# Glove_PCB.net
KiCad netlist of a schematic drawn in EAGLE
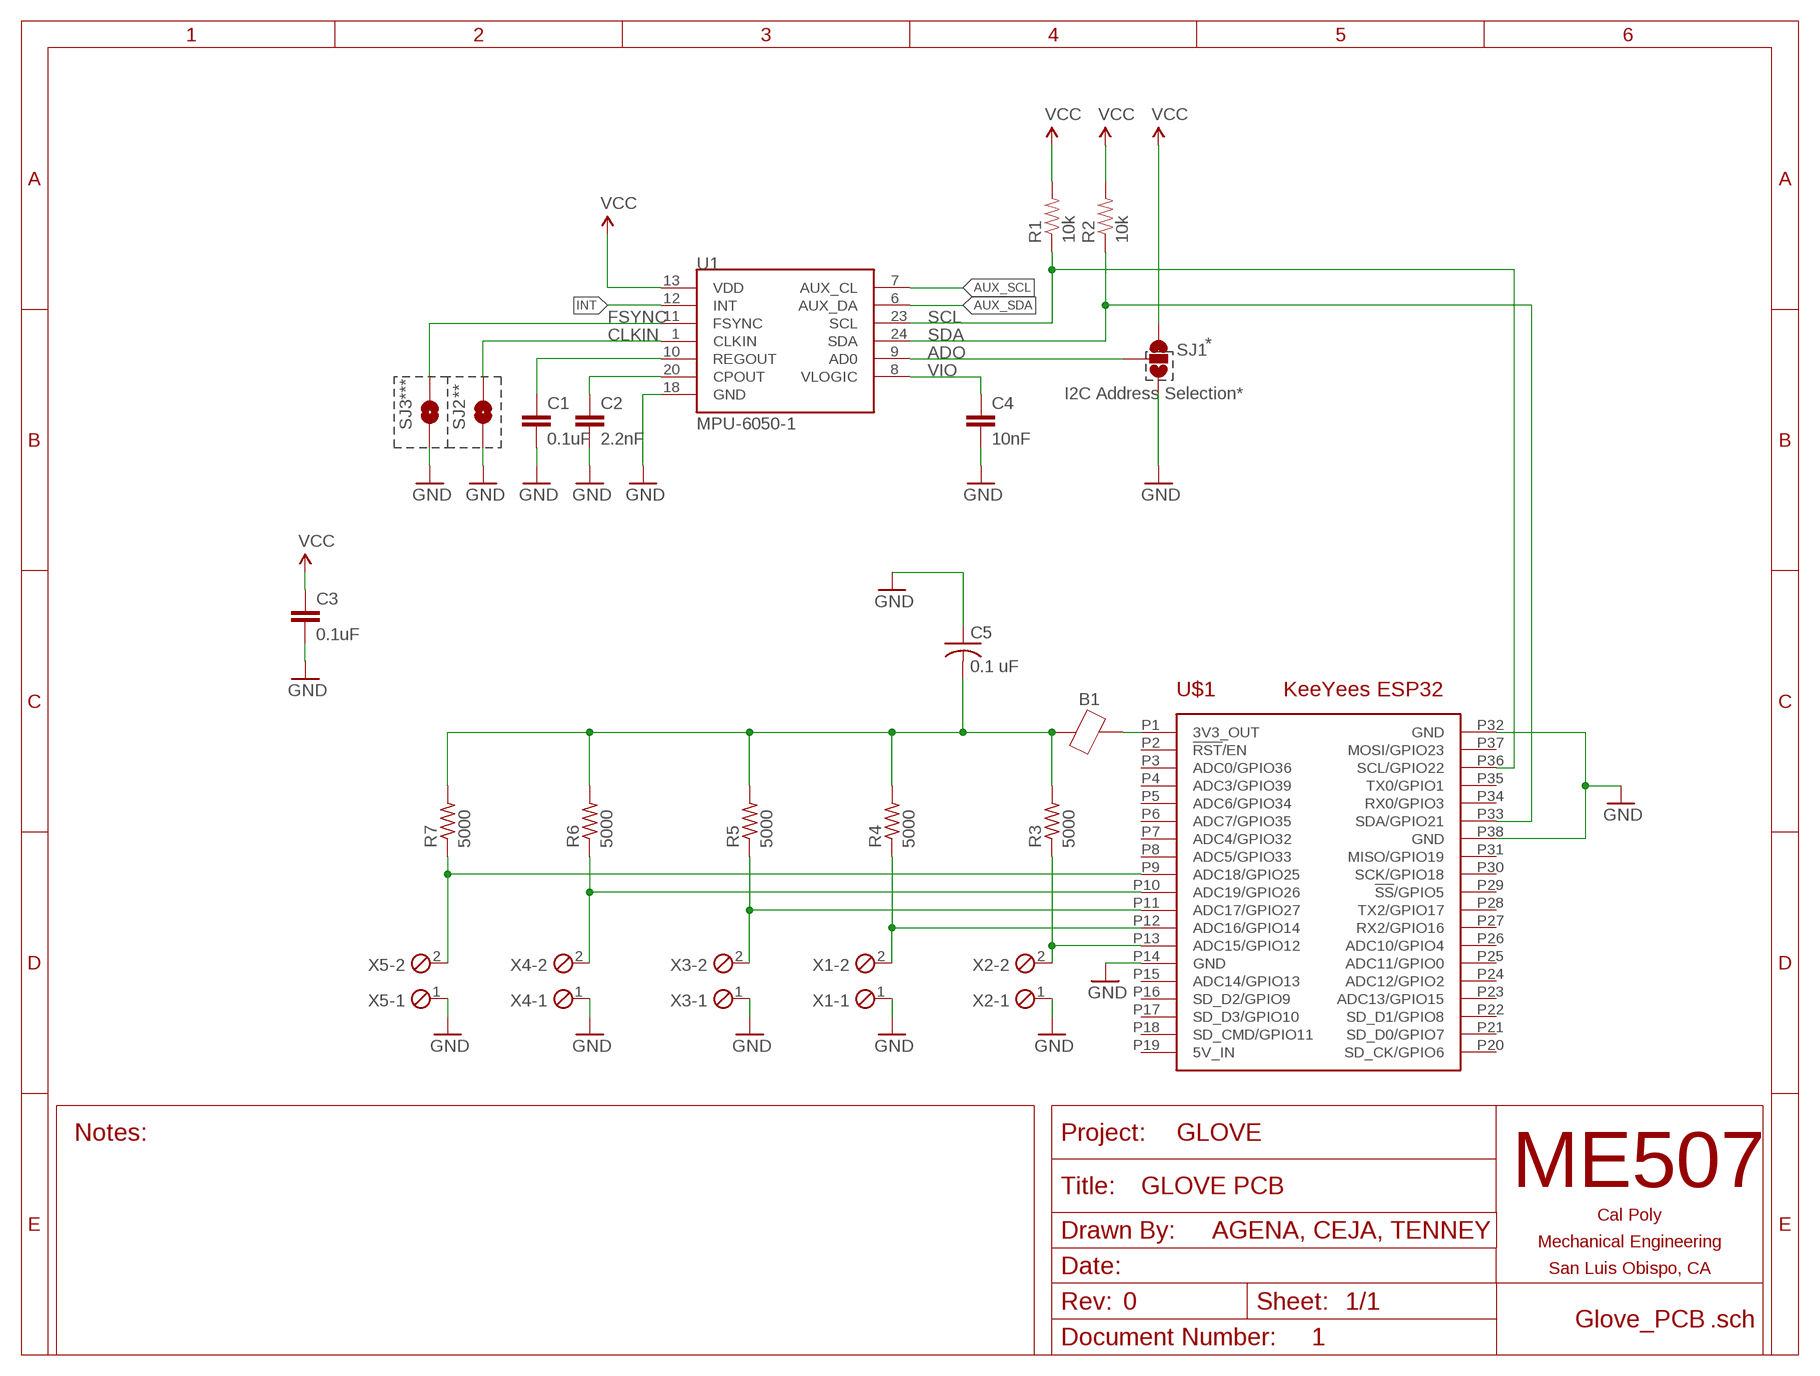
[diagram p0: schematic, sheet 1]

(export (version "E")
  (design (tool "Eeschema 10.0.6"))
  (components
    (comp (ref "B1")
      (value "BEAD0805")
      (footprint "eagle-import:0805")
      (libsource (lib "eagle-import") (part "BEAD0805"))
    )
    (comp (ref "C1")
      (value "0.1uF")
      (footprint "eagle-import:0603-CAP")
      (libsource (lib "eagle-import") (part "CAP0603-CAP"))
    )
    (comp (ref "C2")
      (value "2.2nF")
      (footprint "eagle-import:0603-CAP")
      (libsource (lib "eagle-import") (part "CAP0603-CAP"))
    )
    (comp (ref "C3")
      (value "0.1uF")
      (footprint "eagle-import:0603-CAP")
      (libsource (lib "eagle-import") (part "CAP0603-CAP"))
    )
    (comp (ref "C4")
      (value "10nF")
      (footprint "eagle-import:0603-CAP")
      (libsource (lib "eagle-import") (part "CAP0603-CAP"))
    )
    (comp (ref "C5")
      (value "0.1 uF")
      (footprint "eagle-import:C0805")
      (libsource (lib "eagle-import") (part "C-USC0805"))
    )
    (comp (ref "R1")
      (value "10k")
      (footprint "eagle-import:0603-RES")
      (libsource (lib "eagle-import") (part "RESISTOR0603-RES"))
    )
    (comp (ref "R2")
      (value "10k")
      (footprint "eagle-import:0603-RES")
      (libsource (lib "eagle-import") (part "RESISTOR0603-RES"))
    )
    (comp (ref "R3")
      (value "5000")
      (footprint "eagle-import:R0805")
      (libsource (lib "eagle-import") (part "R-US_R0805"))
    )
    (comp (ref "R4")
      (value "5000")
      (footprint "eagle-import:R0805")
      (libsource (lib "eagle-import") (part "R-US_R0805"))
    )
    (comp (ref "R5")
      (value "5000")
      (footprint "eagle-import:R0805")
      (libsource (lib "eagle-import") (part "R-US_R0805"))
    )
    (comp (ref "R6")
      (value "5000")
      (footprint "eagle-import:R0805")
      (libsource (lib "eagle-import") (part "R-US_R0805"))
    )
    (comp (ref "R7")
      (value "5000")
      (footprint "eagle-import:R0805")
      (libsource (lib "eagle-import") (part "R-US_R0805"))
    )
    (comp (ref "SJ1")
      (value "SOLDERJUMPER_2WAYPASTE2&3")
      (footprint "eagle-import:SJ_3_PASTE2&3")
      (libsource (lib "eagle-import") (part "SOLDERJUMPER_2WAYPASTE2&3"))
    )
    (comp (ref "SJ2")
      (value "SOLDERJUMPERTRACE")
      (footprint "eagle-import:SJ_2S-TRACE")
      (libsource (lib "eagle-import") (part "SOLDERJUMPERTRACE"))
    )
    (comp (ref "SJ3")
      (value "SOLDERJUMPERTRACE")
      (footprint "eagle-import:SJ_2S-TRACE")
      (libsource (lib "eagle-import") (part "SOLDERJUMPERTRACE"))
    )
    (comp (ref "U$1")
      (value "KEEYEES_ESP32EXT")
      (footprint "eagle-import:KEEYEES_ESP32_EXTENDED")
      (libsource (lib "eagle-import") (part "KEEYEES_ESP32EXT"))
    )
    (comp (ref "U1")
      (value "MPU-6050-1")
      (footprint "eagle-import:QFN-24-4MM2")
      (libsource (lib "eagle-import") (part "MPU-6050-1"))
    )
    (comp (ref "X1")
      (value "SCREWTERM_2P_254")
      (footprint "eagle-import:2POL254")
      (libsource (lib "eagle-import") (part "SCREWTERM_2P_254"))
    )
    (comp (ref "X2")
      (value "SCREWTERM_2P_254")
      (footprint "eagle-import:2POL254")
      (libsource (lib "eagle-import") (part "SCREWTERM_2P_254"))
    )
    (comp (ref "X3")
      (value "SCREWTERM_2P_254")
      (footprint "eagle-import:2POL254")
      (libsource (lib "eagle-import") (part "SCREWTERM_2P_254"))
    )
    (comp (ref "X4")
      (value "SCREWTERM_2P_254")
      (footprint "eagle-import:2POL254")
      (libsource (lib "eagle-import") (part "SCREWTERM_2P_254"))
    )
    (comp (ref "X5")
      (value "SCREWTERM_2P_254")
      (footprint "eagle-import:2POL254")
      (libsource (lib "eagle-import") (part "SCREWTERM_2P_254"))
    )
  )
  (nets
    (net (code "1") (name "/5V_IN") (class "Default")
      (node (ref "U$1") (pin "P19") (pinfunction "5V_IN_P19") (pintype "power_in"))
    )
    (net (code "2") (name "/ADO") (class "Default")
      (node (ref "SJ1") (pin "2") (pinfunction "2_2") (pintype "passive"))
      (node (ref "U1") (pin "9") (pinfunction "AD0_9") (pintype "bidirectional"))
    )
    (net (code "3") (name "/CLKIN") (class "Default")
      (node (ref "SJ2") (pin "2") (pinfunction "2_2") (pintype "passive"))
      (node (ref "U1") (pin "1") (pinfunction "CLKIN_1") (pintype "bidirectional"))
    )
    (net (code "4") (name "/FSYNC") (class "Default")
      (node (ref "SJ3") (pin "2") (pinfunction "2_2") (pintype "passive"))
      (node (ref "U1") (pin "11") (pinfunction "FSYNC_11") (pintype "bidirectional"))
    )
    (net (code "5") (name "/SCL") (class "Default")
      (node (ref "R1") (pin "1") (pinfunction "1_1") (pintype "passive"))
      (node (ref "U$1") (pin "P36") (pinfunction "SCL/GPIO22_P36") (pintype "bidirectional"))
      (node (ref "U1") (pin "23") (pinfunction "SCL_23") (pintype "bidirectional"))
    )
    (net (code "6") (name "/SDA") (class "Default")
      (node (ref "R2") (pin "1") (pinfunction "1_1") (pintype "passive"))
      (node (ref "U$1") (pin "P33") (pinfunction "SDA/GPIO21_P33") (pintype "bidirectional"))
      (node (ref "U1") (pin "24") (pinfunction "SDA_24") (pintype "bidirectional"))
    )
    (net (code "7") (name "/VIO") (class "Default")
      (node (ref "C4") (pin "1") (pinfunction "1_1") (pintype "passive"))
      (node (ref "U1") (pin "8") (pinfunction "VLOGIC_8") (pintype "bidirectional"))
    )
    (net (code "8") (name "AUX_SCL") (class "Default")
      (node (ref "U1") (pin "7") (pinfunction "AUX_CL_7") (pintype "bidirectional"))
    )
    (net (code "9") (name "AUX_SDA") (class "Default")
      (node (ref "U1") (pin "6") (pinfunction "AUX_DA_6") (pintype "bidirectional"))
    )
    (net (code "10") (name "GND") (class "Default")
      (node (ref "C1") (pin "2") (pinfunction "2_2") (pintype "passive"))
      (node (ref "C2") (pin "2") (pinfunction "2_2") (pintype "passive"))
      (node (ref "C3") (pin "2") (pinfunction "2_2") (pintype "passive"))
      (node (ref "C4") (pin "2") (pinfunction "2_2") (pintype "passive"))
      (node (ref "C5") (pin "1") (pinfunction "1_1") (pintype "passive"))
      (node (ref "SJ1") (pin "3") (pinfunction "3_3") (pintype "passive"))
      (node (ref "SJ2") (pin "1") (pinfunction "1_1") (pintype "passive"))
      (node (ref "SJ3") (pin "1") (pinfunction "1_1") (pintype "passive"))
      (node (ref "U$1") (pin "P14") (pinfunction "GND_P14") (pintype "power_in"))
      (node (ref "U$1") (pin "P32") (pinfunction "GND_P32") (pintype "power_in"))
      (node (ref "U$1") (pin "P38") (pinfunction "GND_P38") (pintype "power_in"))
      (node (ref "U1") (pin "18") (pinfunction "GND_18") (pintype "bidirectional"))
      (node (ref "X1") (pin "1") (pinfunction "1_1") (pintype "passive"))
      (node (ref "X2") (pin "1") (pinfunction "1_1") (pintype "passive"))
      (node (ref "X3") (pin "1") (pinfunction "1_1") (pintype "passive"))
      (node (ref "X4") (pin "1") (pinfunction "1_1") (pintype "passive"))
      (node (ref "X5") (pin "1") (pinfunction "1_1") (pintype "passive"))
    )
    (net (code "11") (name "INT") (class "Default")
      (node (ref "U1") (pin "12") (pinfunction "INT_12") (pintype "bidirectional"))
    )
    (net (code "12") (name "Net-(B1-Pad1)") (class "Default")
      (node (ref "B1") (pin "1") (pinfunction "1_1") (pintype "bidirectional"))
      (node (ref "C5") (pin "2") (pinfunction "2_2") (pintype "passive"))
      (node (ref "R3") (pin "2") (pinfunction "2_2") (pintype "passive"))
      (node (ref "R4") (pin "2") (pinfunction "2_2") (pintype "passive"))
      (node (ref "R5") (pin "2") (pinfunction "2_2") (pintype "passive"))
      (node (ref "R6") (pin "2") (pinfunction "2_2") (pintype "passive"))
      (node (ref "R7") (pin "2") (pinfunction "2_2") (pintype "passive"))
    )
    (net (code "13") (name "Net-(U$1-3V3_OUT)") (class "Default")
      (node (ref "B1") (pin "2") (pinfunction "2_2") (pintype "bidirectional"))
      (node (ref "U$1") (pin "P1") (pinfunction "3V3_OUT_P1") (pintype "power_in"))
    )
    (net (code "14") (name "Net-(U$1-ADC15{slash}GPIO12)") (class "Default")
      (node (ref "R3") (pin "1") (pinfunction "1_1") (pintype "passive"))
      (node (ref "U$1") (pin "P13") (pinfunction "ADC15/GPIO12_P13") (pintype "bidirectional"))
      (node (ref "X2") (pin "2") (pinfunction "1_2") (pintype "passive"))
    )
    (net (code "15") (name "Net-(U$1-ADC16{slash}GPIO14)") (class "Default")
      (node (ref "R4") (pin "1") (pinfunction "1_1") (pintype "passive"))
      (node (ref "U$1") (pin "P12") (pinfunction "ADC16/GPIO14_P12") (pintype "bidirectional"))
      (node (ref "X1") (pin "2") (pinfunction "1_2") (pintype "passive"))
    )
    (net (code "16") (name "Net-(U$1-ADC17{slash}GPIO27)") (class "Default")
      (node (ref "R5") (pin "1") (pinfunction "1_1") (pintype "passive"))
      (node (ref "U$1") (pin "P11") (pinfunction "ADC17/GPIO27_P11") (pintype "bidirectional"))
      (node (ref "X3") (pin "2") (pinfunction "1_2") (pintype "passive"))
    )
    (net (code "17") (name "Net-(U$1-ADC18{slash}GPIO25)") (class "Default")
      (node (ref "R7") (pin "1") (pinfunction "1_1") (pintype "passive"))
      (node (ref "U$1") (pin "P9") (pinfunction "ADC18/GPIO25_P9") (pintype "bidirectional"))
      (node (ref "X5") (pin "2") (pinfunction "1_2") (pintype "passive"))
    )
    (net (code "18") (name "Net-(U$1-ADC19{slash}GPIO26)") (class "Default")
      (node (ref "R6") (pin "1") (pinfunction "1_1") (pintype "passive"))
      (node (ref "U$1") (pin "P10") (pinfunction "ADC19/GPIO26_P10") (pintype "bidirectional"))
      (node (ref "X4") (pin "2") (pinfunction "1_2") (pintype "passive"))
    )
    (net (code "19") (name "Net-(U1-CPOUT)") (class "Default")
      (node (ref "C2") (pin "1") (pinfunction "1_1") (pintype "passive"))
      (node (ref "U1") (pin "20") (pinfunction "CPOUT_20") (pintype "bidirectional"))
    )
    (net (code "20") (name "Net-(U1-REGOUT)") (class "Default")
      (node (ref "C1") (pin "1") (pinfunction "1_1") (pintype "passive"))
      (node (ref "U1") (pin "10") (pinfunction "REGOUT_10") (pintype "bidirectional"))
    )
    (net (code "21") (name "VCC") (class "Default")
      (node (ref "C3") (pin "1") (pinfunction "1_1") (pintype "passive"))
      (node (ref "R1") (pin "2") (pinfunction "2_2") (pintype "passive"))
      (node (ref "R2") (pin "2") (pinfunction "2_2") (pintype "passive"))
      (node (ref "SJ1") (pin "1") (pinfunction "1_1") (pintype "passive"))
      (node (ref "U1") (pin "13") (pinfunction "VDD_13") (pintype "bidirectional"))
    )
    (net (code "22") (name "unconnected-(U$1-ADC0{slash}GPIO36-PadP3)") (class "Default")
      (node (ref "U$1") (pin "P3") (pinfunction "ADC0/GPIO36_P3") (pintype "bidirectional"))
    )
    (net (code "23") (name "unconnected-(U$1-ADC3{slash}GPIO39-PadP4)") (class "Default")
      (node (ref "U$1") (pin "P4") (pinfunction "ADC3/GPIO39_P4") (pintype "bidirectional"))
    )
    (net (code "24") (name "unconnected-(U$1-ADC4{slash}GPIO32-PadP7)") (class "Default")
      (node (ref "U$1") (pin "P7") (pinfunction "ADC4/GPIO32_P7") (pintype "bidirectional"))
    )
    (net (code "25") (name "unconnected-(U$1-ADC5{slash}GPIO33-PadP8)") (class "Default")
      (node (ref "U$1") (pin "P8") (pinfunction "ADC5/GPIO33_P8") (pintype "bidirectional"))
    )
    (net (code "26") (name "unconnected-(U$1-ADC6{slash}GPIO34-PadP5)") (class "Default")
      (node (ref "U$1") (pin "P5") (pinfunction "ADC6/GPIO34_P5") (pintype "bidirectional"))
    )
    (net (code "27") (name "unconnected-(U$1-ADC7{slash}GPIO35-PadP6)") (class "Default")
      (node (ref "U$1") (pin "P6") (pinfunction "ADC7/GPIO35_P6") (pintype "bidirectional"))
    )
    (net (code "28") (name "unconnected-(U$1-ADC10{slash}GPIO4-PadP26)") (class "Default")
      (node (ref "U$1") (pin "P26") (pinfunction "ADC10/GPIO4_P26") (pintype "bidirectional"))
    )
    (net (code "29") (name "unconnected-(U$1-ADC11{slash}GPIO0-PadP25)") (class "Default")
      (node (ref "U$1") (pin "P25") (pinfunction "ADC11/GPIO0_P25") (pintype "bidirectional"))
    )
    (net (code "30") (name "unconnected-(U$1-ADC12{slash}GPIO2-PadP24)") (class "Default")
      (node (ref "U$1") (pin "P24") (pinfunction "ADC12/GPIO2_P24") (pintype "bidirectional"))
    )
    (net (code "31") (name "unconnected-(U$1-ADC13{slash}GPIO15-PadP23)") (class "Default")
      (node (ref "U$1") (pin "P23") (pinfunction "ADC13/GPIO15_P23") (pintype "bidirectional"))
    )
    (net (code "32") (name "unconnected-(U$1-ADC14{slash}GPIO13-PadP15)") (class "Default")
      (node (ref "U$1") (pin "P15") (pinfunction "ADC14/GPIO13_P15") (pintype "bidirectional"))
    )
    (net (code "33") (name "unconnected-(U$1-MISO{slash}GPIO19-PadP31)") (class "Default")
      (node (ref "U$1") (pin "P31") (pinfunction "MISO/GPIO19_P31") (pintype "bidirectional"))
    )
    (net (code "34") (name "unconnected-(U$1-MOSI{slash}GPIO23-PadP37)") (class "Default")
      (node (ref "U$1") (pin "P37") (pinfunction "MOSI/GPIO23_P37") (pintype "bidirectional"))
    )
    (net (code "35") (name "unconnected-(U$1-RX0{slash}GPIO3-PadP34)") (class "Default")
      (node (ref "U$1") (pin "P34") (pinfunction "RX0/GPIO3_P34") (pintype "bidirectional"))
    )
    (net (code "36") (name "unconnected-(U$1-RX2{slash}GPIO16-PadP27)") (class "Default")
      (node (ref "U$1") (pin "P27") (pinfunction "RX2/GPIO16_P27") (pintype "bidirectional"))
    )
    (net (code "37") (name "unconnected-(U$1-SCK{slash}GPIO18-PadP30)") (class "Default")
      (node (ref "U$1") (pin "P30") (pinfunction "SCK/GPIO18_P30") (pintype "bidirectional"))
    )
    (net (code "38") (name "unconnected-(U$1-SD_CK{slash}GPIO6-PadP20)") (class "Default")
      (node (ref "U$1") (pin "P20") (pinfunction "SD_CK/GPIO6_P20") (pintype "bidirectional"))
    )
    (net (code "39") (name "unconnected-(U$1-SD_CMD{slash}GPIO11-PadP18)") (class "Default")
      (node (ref "U$1") (pin "P18") (pinfunction "SD_CMD/GPIO11_P18") (pintype "bidirectional"))
    )
    (net (code "40") (name "unconnected-(U$1-SD_D0{slash}GPIO7-PadP21)") (class "Default")
      (node (ref "U$1") (pin "P21") (pinfunction "SD_D0/GPIO7_P21") (pintype "bidirectional"))
    )
    (net (code "41") (name "unconnected-(U$1-SD_D1{slash}GPIO8-PadP22)") (class "Default")
      (node (ref "U$1") (pin "P22") (pinfunction "SD_D1/GPIO8_P22") (pintype "bidirectional"))
    )
    (net (code "42") (name "unconnected-(U$1-SD_D2{slash}GPIO9-PadP16)") (class "Default")
      (node (ref "U$1") (pin "P16") (pinfunction "SD_D2/GPIO9_P16") (pintype "bidirectional"))
    )
    (net (code "43") (name "unconnected-(U$1-SD_D3{slash}GPIO10-PadP17)") (class "Default")
      (node (ref "U$1") (pin "P17") (pinfunction "SD_D3/GPIO10_P17") (pintype "bidirectional"))
    )
    (net (code "44") (name "unconnected-(U$1-TX0{slash}GPIO1-PadP35)") (class "Default")
      (node (ref "U$1") (pin "P35") (pinfunction "TX0/GPIO1_P35") (pintype "bidirectional"))
    )
    (net (code "45") (name "unconnected-(U$1-TX2{slash}GPIO17-PadP28)") (class "Default")
      (node (ref "U$1") (pin "P28") (pinfunction "TX2/GPIO17_P28") (pintype "bidirectional"))
    )
    (net (code "46") (name "unconnected-(U$1-~{RST}{slash}EN-PadP2)") (class "Default")
      (node (ref "U$1") (pin "P2") (pinfunction "~{RST}/EN_P2") (pintype "input"))
    )
    (net (code "47") (name "unconnected-(U$1-~{SS}{slash}GPIO5-PadP29)") (class "Default")
      (node (ref "U$1") (pin "P29") (pinfunction "~{SS}/GPIO5_P29") (pintype "bidirectional"))
    )
  )
)
